# Large_Digit_Driver.net
KiCad netlist of a schematic drawn in EAGLE
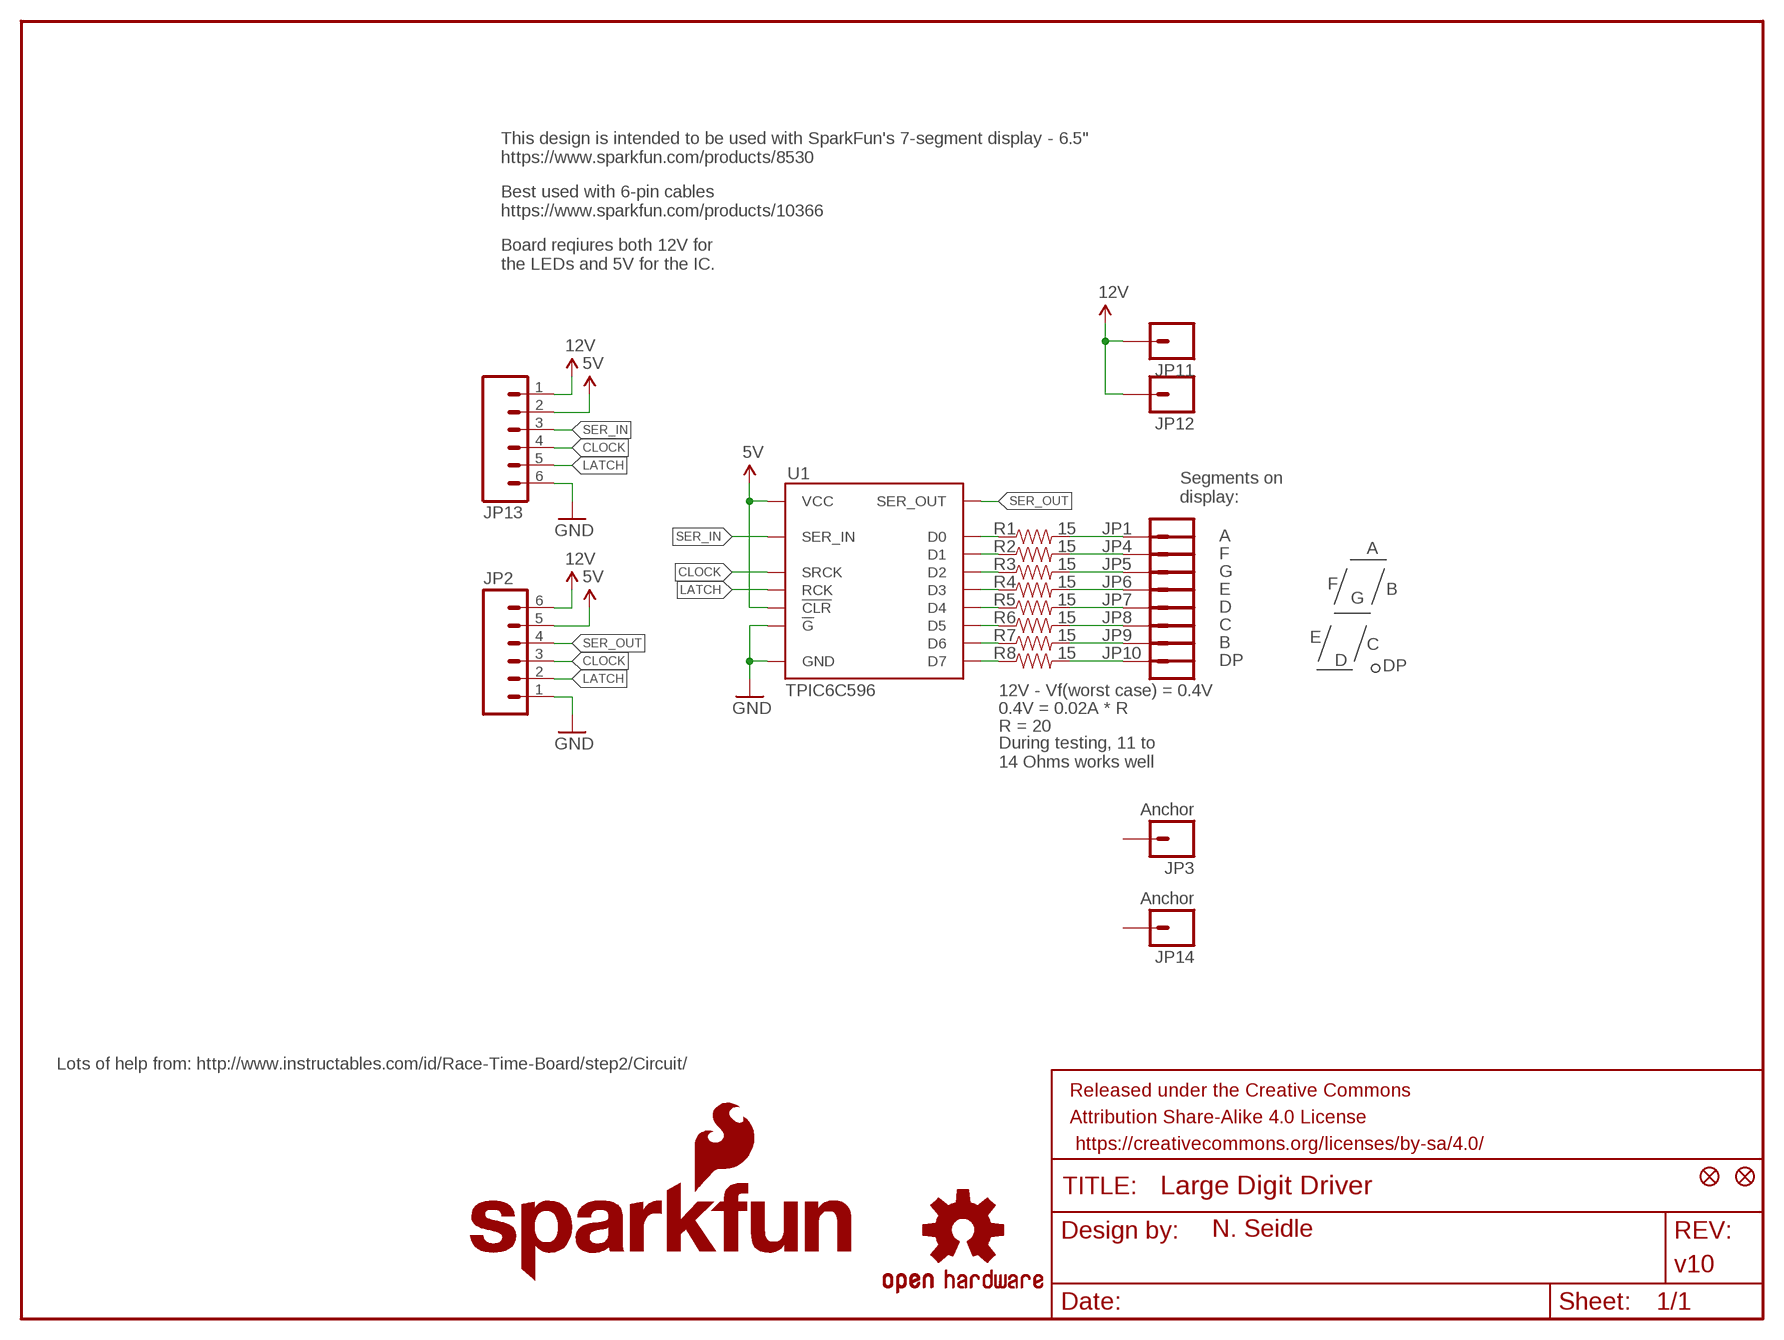
[diagram p0: schematic, sheet 1]

(export (version "E")
  (design (tool "Eeschema 10.0.6"))
  (components
    (comp (ref "FID1")
      (value "FIDUCIAL1X2")
      (footprint "eagle-import:FIDUCIAL-1X2")
      (libsource (lib "eagle-import") (part "FIDUCIAL1X2"))
    )
    (comp (ref "FID2")
      (value "FIDUCIAL1X2")
      (footprint "eagle-import:FIDUCIAL-1X2")
      (libsource (lib "eagle-import") (part "FIDUCIAL1X2"))
    )
    (comp (ref "FRAME1")
      (value "FRAME-LETTER")
      (footprint "eagle-import:CREATIVE_COMMONS")
      (fields (field (name "DESIGNER") "N. Seidle") (field (name "VERSION") "v10"))
      (libsource (lib "eagle-import") (part "FRAME-LETTER"))
    )
    (comp (ref "JP1")
      (value "M01PTH_LONGPAD")
      (footprint "eagle-import:1X01_LONGPAD")
      (libsource (lib "eagle-import") (part "M01PTH_LONGPAD"))
    )
    (comp (ref "JP2")
      (value "M06SMD")
      (footprint "eagle-import:1X06-SMD")
      (libsource (lib "eagle-import") (part "M06SMD"))
    )
    (comp (ref "JP3")
      (value "Anchor")
      (footprint "eagle-import:1X01_LONGPAD")
      (libsource (lib "eagle-import") (part "M01PTH_LONGPAD"))
    )
    (comp (ref "JP4")
      (value "M01PTH_LONGPAD")
      (footprint "eagle-import:1X01_LONGPAD")
      (libsource (lib "eagle-import") (part "M01PTH_LONGPAD"))
    )
    (comp (ref "JP5")
      (value "M01PTH_LONGPAD")
      (footprint "eagle-import:1X01_LONGPAD")
      (libsource (lib "eagle-import") (part "M01PTH_LONGPAD"))
    )
    (comp (ref "JP6")
      (value "M01PTH_LONGPAD")
      (footprint "eagle-import:1X01_LONGPAD")
      (libsource (lib "eagle-import") (part "M01PTH_LONGPAD"))
    )
    (comp (ref "JP7")
      (value "M01PTH_LONGPAD")
      (footprint "eagle-import:1X01_LONGPAD")
      (libsource (lib "eagle-import") (part "M01PTH_LONGPAD"))
    )
    (comp (ref "JP8")
      (value "M01PTH_LONGPAD")
      (footprint "eagle-import:1X01_LONGPAD")
      (libsource (lib "eagle-import") (part "M01PTH_LONGPAD"))
    )
    (comp (ref "JP9")
      (value "M01PTH_LONGPAD")
      (footprint "eagle-import:1X01_LONGPAD")
      (libsource (lib "eagle-import") (part "M01PTH_LONGPAD"))
    )
    (comp (ref "JP10")
      (value "M01PTH_LONGPAD")
      (footprint "eagle-import:1X01_LONGPAD")
      (libsource (lib "eagle-import") (part "M01PTH_LONGPAD"))
    )
    (comp (ref "JP11")
      (value "M01PTH_LONGPAD")
      (footprint "eagle-import:1X01_LONGPAD")
      (libsource (lib "eagle-import") (part "M01PTH_LONGPAD"))
    )
    (comp (ref "JP12")
      (value "M01PTH_LONGPAD")
      (footprint "eagle-import:1X01_LONGPAD")
      (libsource (lib "eagle-import") (part "M01PTH_LONGPAD"))
    )
    (comp (ref "JP13")
      (value "M06SMD")
      (footprint "eagle-import:1X06-SMD")
      (libsource (lib "eagle-import") (part "M06SMD"))
    )
    (comp (ref "JP14")
      (value "Anchor")
      (footprint "eagle-import:1X01_LONGPAD")
      (libsource (lib "eagle-import") (part "M01PTH_LONGPAD"))
    )
    (comp (ref "LOGO1")
      (value "SFE_LOGO_NAME_FLAME.1_INCH")
      (footprint "eagle-import:SFE_LOGO_NAME_FLAME_.1")
      (libsource (lib "eagle-import") (part "SFE_LOGO_NAME_FLAME.1_INCH"))
    )
    (comp (ref "LOGO2")
      (value "OSHW-LOGOS")
      (footprint "eagle-import:OSHW-LOGO-S")
      (libsource (lib "eagle-import") (part "OSHW-LOGOS"))
    )
    (comp (ref "R1")
      (value "15")
      (footprint "eagle-import:0603-RES")
      (libsource (lib "eagle-import") (part "15OHM-1/10W-1%(0603)0603"))
    )
    (comp (ref "R2")
      (value "15")
      (footprint "eagle-import:0603-RES")
      (libsource (lib "eagle-import") (part "15OHM-1/10W-1%(0603)0603"))
    )
    (comp (ref "R3")
      (value "15")
      (footprint "eagle-import:0603-RES")
      (libsource (lib "eagle-import") (part "15OHM-1/10W-1%(0603)0603"))
    )
    (comp (ref "R4")
      (value "15")
      (footprint "eagle-import:0603-RES")
      (libsource (lib "eagle-import") (part "15OHM-1/10W-1%(0603)0603"))
    )
    (comp (ref "R5")
      (value "15")
      (footprint "eagle-import:0603-RES")
      (libsource (lib "eagle-import") (part "15OHM-1/10W-1%(0603)0603"))
    )
    (comp (ref "R6")
      (value "15")
      (footprint "eagle-import:0603-RES")
      (libsource (lib "eagle-import") (part "15OHM-1/10W-1%(0603)0603"))
    )
    (comp (ref "R7")
      (value "15")
      (footprint "eagle-import:0603-RES")
      (libsource (lib "eagle-import") (part "15OHM-1/10W-1%(0603)0603"))
    )
    (comp (ref "R8")
      (value "15")
      (footprint "eagle-import:0603-RES")
      (libsource (lib "eagle-import") (part "15OHM-1/10W-1%(0603)0603"))
    )
    (comp (ref "U1")
      (value "TPIC6C596")
      (footprint "eagle-import:SO016")
      (libsource (lib "eagle-import") (part "TPIC6C596SOIC"))
    )
  )
  (nets
    (net (code "1") (name "5V") (class "Default")
      (node (ref "JP13") (pin "2") (pinfunction "2_2") (pintype "passive"))
      (node (ref "JP2") (pin "5") (pinfunction "5_5") (pintype "passive"))
      (node (ref "U1") (pin "1") (pinfunction "VCC_1") (pintype "power_in"))
      (node (ref "U1") (pin "7") (pinfunction "~{CLR}_7") (pintype "input"))
    )
    (net (code "2") (name "12V") (class "Default")
      (node (ref "JP11") (pin "1") (pinfunction "1_1") (pintype "passive"))
      (node (ref "JP12") (pin "1") (pinfunction "1_1") (pintype "passive"))
      (node (ref "JP13") (pin "1") (pinfunction "1_1") (pintype "passive"))
      (node (ref "JP2") (pin "6") (pinfunction "6_6") (pintype "passive"))
    )
    (net (code "3") (name "CLOCK") (class "Default")
      (node (ref "JP13") (pin "4") (pinfunction "4_4") (pintype "passive"))
      (node (ref "JP2") (pin "3") (pinfunction "3_3") (pintype "passive"))
      (node (ref "U1") (pin "15") (pinfunction "SRCK_15") (pintype "input"))
    )
    (net (code "4") (name "GND") (class "Default")
      (node (ref "JP13") (pin "6") (pinfunction "6_6") (pintype "passive"))
      (node (ref "JP2") (pin "1") (pinfunction "1_1") (pintype "passive"))
      (node (ref "U1") (pin "16") (pinfunction "GND_16") (pintype "power_in"))
      (node (ref "U1") (pin "8") (pinfunction "~{G}_8") (pintype "input"))
    )
    (net (code "5") (name "LATCH") (class "Default")
      (node (ref "JP13") (pin "5") (pinfunction "5_5") (pintype "passive"))
      (node (ref "JP2") (pin "2") (pinfunction "2_2") (pintype "passive"))
      (node (ref "U1") (pin "10") (pinfunction "RCK_10") (pintype "input"))
    )
    (net (code "6") (name "Net-(JP1-Pad1)") (class "Default")
      (node (ref "JP1") (pin "1") (pinfunction "1_1") (pintype "passive"))
      (node (ref "R1") (pin "2") (pinfunction "2_2") (pintype "passive"))
    )
    (net (code "7") (name "Net-(JP4-Pad1)") (class "Default")
      (node (ref "JP4") (pin "1") (pinfunction "1_1") (pintype "passive"))
      (node (ref "R2") (pin "2") (pinfunction "2_2") (pintype "passive"))
    )
    (net (code "8") (name "Net-(JP5-Pad1)") (class "Default")
      (node (ref "JP5") (pin "1") (pinfunction "1_1") (pintype "passive"))
      (node (ref "R3") (pin "2") (pinfunction "2_2") (pintype "passive"))
    )
    (net (code "9") (name "Net-(JP6-Pad1)") (class "Default")
      (node (ref "JP6") (pin "1") (pinfunction "1_1") (pintype "passive"))
      (node (ref "R4") (pin "2") (pinfunction "2_2") (pintype "passive"))
    )
    (net (code "10") (name "Net-(JP7-Pad1)") (class "Default")
      (node (ref "JP7") (pin "1") (pinfunction "1_1") (pintype "passive"))
      (node (ref "R5") (pin "2") (pinfunction "2_2") (pintype "passive"))
    )
    (net (code "11") (name "Net-(JP8-Pad1)") (class "Default")
      (node (ref "JP8") (pin "1") (pinfunction "1_1") (pintype "passive"))
      (node (ref "R6") (pin "2") (pinfunction "2_2") (pintype "passive"))
    )
    (net (code "12") (name "Net-(JP9-Pad1)") (class "Default")
      (node (ref "JP9") (pin "1") (pinfunction "1_1") (pintype "passive"))
      (node (ref "R7") (pin "2") (pinfunction "2_2") (pintype "passive"))
    )
    (net (code "13") (name "Net-(JP10-Pad1)") (class "Default")
      (node (ref "JP10") (pin "1") (pinfunction "1_1") (pintype "passive"))
      (node (ref "R8") (pin "2") (pinfunction "2_2") (pintype "passive"))
    )
    (net (code "14") (name "Net-(U1-D0)") (class "Default")
      (node (ref "R1") (pin "1") (pinfunction "1_1") (pintype "passive"))
      (node (ref "U1") (pin "3") (pinfunction "D0_3") (pintype "output"))
    )
    (net (code "15") (name "Net-(U1-D1)") (class "Default")
      (node (ref "R2") (pin "1") (pinfunction "1_1") (pintype "passive"))
      (node (ref "U1") (pin "4") (pinfunction "D1_4") (pintype "output"))
    )
    (net (code "16") (name "Net-(U1-D2)") (class "Default")
      (node (ref "R3") (pin "1") (pinfunction "1_1") (pintype "passive"))
      (node (ref "U1") (pin "5") (pinfunction "D2_5") (pintype "output"))
    )
    (net (code "17") (name "Net-(U1-D3)") (class "Default")
      (node (ref "R4") (pin "1") (pinfunction "1_1") (pintype "passive"))
      (node (ref "U1") (pin "6") (pinfunction "D3_6") (pintype "output"))
    )
    (net (code "18") (name "Net-(U1-D4)") (class "Default")
      (node (ref "R5") (pin "1") (pinfunction "1_1") (pintype "passive"))
      (node (ref "U1") (pin "11") (pinfunction "D4_11") (pintype "output"))
    )
    (net (code "19") (name "Net-(U1-D5)") (class "Default")
      (node (ref "R6") (pin "1") (pinfunction "1_1") (pintype "passive"))
      (node (ref "U1") (pin "12") (pinfunction "D5_12") (pintype "output"))
    )
    (net (code "20") (name "Net-(U1-D6)") (class "Default")
      (node (ref "R7") (pin "1") (pinfunction "1_1") (pintype "passive"))
      (node (ref "U1") (pin "13") (pinfunction "D6_13") (pintype "output"))
    )
    (net (code "21") (name "Net-(U1-D7)") (class "Default")
      (node (ref "R8") (pin "1") (pinfunction "1_1") (pintype "passive"))
      (node (ref "U1") (pin "14") (pinfunction "D7_14") (pintype "output"))
    )
    (net (code "22") (name "SER_IN") (class "Default")
      (node (ref "JP13") (pin "3") (pinfunction "3_3") (pintype "passive"))
      (node (ref "U1") (pin "2") (pinfunction "SER_IN_2") (pintype "input"))
    )
    (net (code "23") (name "SER_OUT") (class "Default")
      (node (ref "JP2") (pin "4") (pinfunction "4_4") (pintype "passive"))
      (node (ref "U1") (pin "9") (pinfunction "SER_OUT_9") (pintype "output"))
    )
    (net (code "24") (name "unconnected-(JP3-Pad1)") (class "Default")
      (node (ref "JP3") (pin "1") (pinfunction "1_1") (pintype "passive"))
    )
    (net (code "25") (name "unconnected-(JP14-Pad1)") (class "Default")
      (node (ref "JP14") (pin "1") (pinfunction "1_1") (pintype "passive"))
    )
  )
)
